# BOTTOM-BOARD_SCH.net
KiCad netlist of a schematic drawn in EAGLE
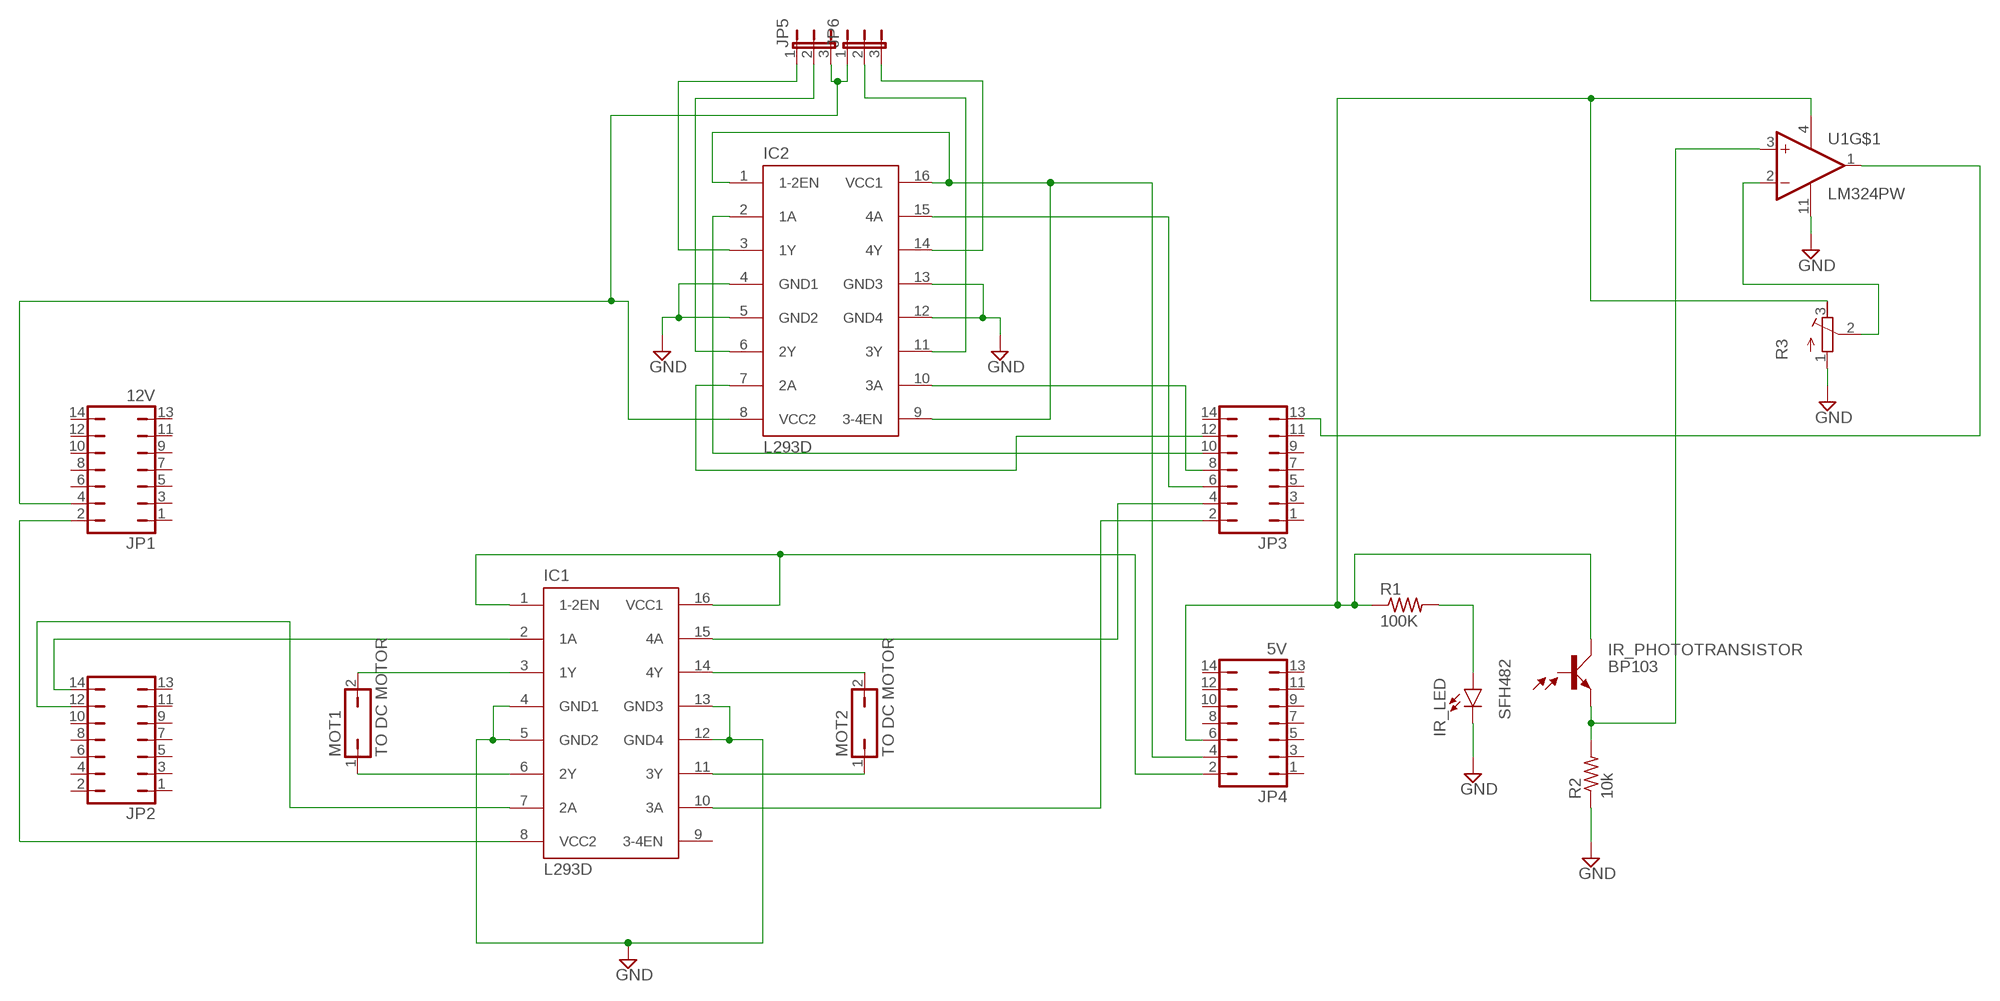
[diagram p0: schematic, sheet 1]

(export (version "E")
  (design (tool "Eeschema 10.0.6"))
  (components
    (comp (ref "IC1")
      (value "L293D")
      (footprint "eagle-import:DIL16")
      (libsource (lib "eagle-import") (part "L293D"))
    )
    (comp (ref "IC2")
      (value "L293D")
      (footprint "eagle-import:DIL16")
      (libsource (lib "eagle-import") (part "L293D"))
    )
    (comp (ref "IR_LED")
      (value "SFH482")
      (footprint "eagle-import:SFH482")
      (libsource (lib "eagle-import") (part "SFH482"))
    )
    (comp (ref "IR_PHOTOTRANSISTOR")
      (value "BP103")
      (footprint "eagle-import:BP103")
      (libsource (lib "eagle-import") (part "BP103"))
    )
    (comp (ref "JP1")
      (value "12V")
      (footprint "eagle-import:JP7Q")
      (libsource (lib "eagle-import") (part "JP7Q"))
    )
    (comp (ref "JP2")
      (value "JP7Q")
      (footprint "eagle-import:JP7Q")
      (libsource (lib "eagle-import") (part "JP7Q"))
    )
    (comp (ref "JP3")
      (value "JP7Q")
      (footprint "eagle-import:JP7Q")
      (libsource (lib "eagle-import") (part "JP7Q"))
    )
    (comp (ref "JP4")
      (value "5V")
      (footprint "eagle-import:JP7Q")
      (libsource (lib "eagle-import") (part "JP7Q"))
    )
    (comp (ref "JP5")
      (value "JP2E")
      (footprint "eagle-import:JP2")
      (libsource (lib "eagle-import") (part "JP2E"))
    )
    (comp (ref "JP6")
      (value "JP2E")
      (footprint "eagle-import:JP2")
      (libsource (lib "eagle-import") (part "JP2E"))
    )
    (comp (ref "MOT1")
      (value "TO DC MOTOR")
      (footprint "eagle-import:JP1")
      (libsource (lib "eagle-import") (part "JP1Q"))
    )
    (comp (ref "MOT2")
      (value "TO DC MOTOR")
      (footprint "eagle-import:JP1")
      (libsource (lib "eagle-import") (part "JP1Q"))
    )
    (comp (ref "R1")
      (value "100K")
      (footprint "eagle-import:0204_5")
      (libsource (lib "eagle-import") (part "R-US_0204/5"))
    )
    (comp (ref "R2")
      (value "10k")
      (footprint "eagle-import:0204_5")
      (libsource (lib "eagle-import") (part "R-US_0204/5"))
    )
    (comp (ref "R3")
      (value "R-TRIMMTSM53YL")
      (footprint "eagle-import:RTRIMTSM53YL")
      (libsource (lib "eagle-import") (part "R-TRIMMTSM53YL"))
    )
    (comp (ref "U1")
      (value "LM324PW")
      (footprint "eagle-import:SOP65P640X120-14N")
      (fields (field (name "MF") "Texas Instruments"))
      (libsource (lib "eagle-import") (part "LM324PW"))
    )
  )
  (nets
    (net (code "1") (name "GND") (class "Default")
      (node (ref "IC1") (pin "12") (pinfunction "GND4_12") (pintype "power_in"))
      (node (ref "IC1") (pin "13") (pinfunction "GND3_13") (pintype "power_in"))
      (node (ref "IC1") (pin "4") (pinfunction "GND1_4") (pintype "power_in"))
      (node (ref "IC1") (pin "5") (pinfunction "GND2_5") (pintype "power_in"))
      (node (ref "IC2") (pin "12") (pinfunction "GND4_12") (pintype "power_in"))
      (node (ref "IC2") (pin "13") (pinfunction "GND3_13") (pintype "power_in"))
      (node (ref "IC2") (pin "4") (pinfunction "GND1_4") (pintype "power_in"))
      (node (ref "IC2") (pin "5") (pinfunction "GND2_5") (pintype "power_in"))
      (node (ref "IR_LED") (pin "K") (pinfunction "C_K") (pintype "passive"))
      (node (ref "R2") (pin "1") (pinfunction "1_1") (pintype "passive"))
      (node (ref "R3") (pin "1") (pinfunction "A_1") (pintype "passive"))
      (node (ref "U1") (pin "11") (pinfunction "GND_11") (pintype "power_in"))
    )
    (net (code "2") (name "Net-(IC1-1-2EN)") (class "Default")
      (node (ref "IC1") (pin "1") (pinfunction "1-2EN_1") (pintype "input"))
      (node (ref "IC1") (pin "16") (pinfunction "VCC1_16") (pintype "power_in"))
      (node (ref "JP4") (pin "2") (pinfunction "2_2") (pintype "passive"))
    )
    (net (code "3") (name "Net-(IC1-1A)") (class "Default")
      (node (ref "IC1") (pin "2") (pinfunction "1A_2") (pintype "input"))
      (node (ref "JP2") (pin "14") (pinfunction "14_14") (pintype "passive"))
    )
    (net (code "4") (name "Net-(IC1-1Y)") (class "Default")
      (node (ref "IC1") (pin "3") (pinfunction "1Y_3") (pintype "output"))
      (node (ref "MOT1") (pin "2") (pinfunction "2_2") (pintype "passive"))
    )
    (net (code "5") (name "Net-(IC1-2A)") (class "Default")
      (node (ref "IC1") (pin "7") (pinfunction "2A_7") (pintype "input"))
      (node (ref "JP2") (pin "12") (pinfunction "12_12") (pintype "passive"))
    )
    (net (code "6") (name "Net-(IC1-2Y)") (class "Default")
      (node (ref "IC1") (pin "6") (pinfunction "2Y_6") (pintype "output"))
      (node (ref "MOT1") (pin "1") (pinfunction "1_1") (pintype "passive"))
    )
    (net (code "7") (name "Net-(IC1-3A)") (class "Default")
      (node (ref "IC1") (pin "10") (pinfunction "3A_10") (pintype "input"))
      (node (ref "JP3") (pin "2") (pinfunction "2_2") (pintype "passive"))
    )
    (net (code "8") (name "Net-(IC1-3Y)") (class "Default")
      (node (ref "IC1") (pin "11") (pinfunction "3Y_11") (pintype "output"))
      (node (ref "MOT2") (pin "1") (pinfunction "1_1") (pintype "passive"))
    )
    (net (code "9") (name "Net-(IC1-4A)") (class "Default")
      (node (ref "IC1") (pin "15") (pinfunction "4A_15") (pintype "input"))
      (node (ref "JP3") (pin "4") (pinfunction "4_4") (pintype "passive"))
    )
    (net (code "10") (name "Net-(IC1-4Y)") (class "Default")
      (node (ref "IC1") (pin "14") (pinfunction "4Y_14") (pintype "output"))
      (node (ref "MOT2") (pin "2") (pinfunction "2_2") (pintype "passive"))
    )
    (net (code "11") (name "Net-(IC1-VCC2)") (class "Default")
      (node (ref "IC1") (pin "8") (pinfunction "VCC2_8") (pintype "power_in"))
      (node (ref "JP1") (pin "2") (pinfunction "2_2") (pintype "passive"))
    )
    (net (code "12") (name "Net-(IC2-1-2EN)") (class "Default")
      (node (ref "IC2") (pin "1") (pinfunction "1-2EN_1") (pintype "input"))
      (node (ref "IC2") (pin "16") (pinfunction "VCC1_16") (pintype "power_in"))
      (node (ref "IC2") (pin "9") (pinfunction "3-4EN_9") (pintype "input"))
      (node (ref "JP4") (pin "4") (pinfunction "4_4") (pintype "passive"))
    )
    (net (code "13") (name "Net-(IC2-1A)") (class "Default")
      (node (ref "IC2") (pin "2") (pinfunction "1A_2") (pintype "input"))
      (node (ref "JP3") (pin "10") (pinfunction "10_10") (pintype "passive"))
    )
    (net (code "14") (name "Net-(IC2-1Y)") (class "Default")
      (node (ref "IC2") (pin "3") (pinfunction "1Y_3") (pintype "output"))
      (node (ref "JP5") (pin "1") (pinfunction "1_1") (pintype "passive"))
    )
    (net (code "15") (name "Net-(IC2-2A)") (class "Default")
      (node (ref "IC2") (pin "7") (pinfunction "2A_7") (pintype "input"))
      (node (ref "JP3") (pin "12") (pinfunction "12_12") (pintype "passive"))
    )
    (net (code "16") (name "Net-(IC2-2Y)") (class "Default")
      (node (ref "IC2") (pin "6") (pinfunction "2Y_6") (pintype "output"))
      (node (ref "JP5") (pin "2") (pinfunction "2_2") (pintype "passive"))
    )
    (net (code "17") (name "Net-(IC2-3A)") (class "Default")
      (node (ref "IC2") (pin "10") (pinfunction "3A_10") (pintype "input"))
      (node (ref "JP3") (pin "8") (pinfunction "8_8") (pintype "passive"))
    )
    (net (code "18") (name "Net-(IC2-3Y)") (class "Default")
      (node (ref "IC2") (pin "11") (pinfunction "3Y_11") (pintype "output"))
      (node (ref "JP6") (pin "2") (pinfunction "2_2") (pintype "passive"))
    )
    (net (code "19") (name "Net-(IC2-4A)") (class "Default")
      (node (ref "IC2") (pin "15") (pinfunction "4A_15") (pintype "input"))
      (node (ref "JP3") (pin "6") (pinfunction "6_6") (pintype "passive"))
    )
    (net (code "20") (name "Net-(IC2-4Y)") (class "Default")
      (node (ref "IC2") (pin "14") (pinfunction "4Y_14") (pintype "output"))
      (node (ref "JP6") (pin "3") (pinfunction "3_3") (pintype "passive"))
    )
    (net (code "21") (name "Net-(IC2-VCC2)") (class "Default")
      (node (ref "IC2") (pin "8") (pinfunction "VCC2_8") (pintype "power_in"))
      (node (ref "JP1") (pin "4") (pinfunction "4_4") (pintype "passive"))
      (node (ref "JP5") (pin "3") (pinfunction "3_3") (pintype "passive"))
      (node (ref "JP6") (pin "1") (pinfunction "1_1") (pintype "passive"))
    )
    (net (code "22") (name "Net-(IR_LED-PadA)") (class "Default")
      (node (ref "IR_LED") (pin "A") (pinfunction "A_A") (pintype "passive"))
      (node (ref "R1") (pin "2") (pinfunction "2_2") (pintype "passive"))
    )
    (net (code "23") (name "Net-(R3-E)") (class "Default")
      (node (ref "IR_PHOTOTRANSISTOR") (pin "C") (pinfunction "C_C") (pintype "passive"))
      (node (ref "JP4") (pin "6") (pinfunction "6_6") (pintype "passive"))
      (node (ref "R1") (pin "1") (pinfunction "1_1") (pintype "passive"))
      (node (ref "R3") (pin "3") (pinfunction "E_3") (pintype "passive"))
      (node (ref "U1") (pin "4") (pinfunction "VCC_4") (pintype "power_in"))
    )
    (net (code "24") (name "Net-(R3-S)") (class "Default")
      (node (ref "R3") (pin "2") (pinfunction "S_2") (pintype "passive"))
      (node (ref "U1") (pin "2") (pinfunction "-IN1_2") (pintype "input"))
    )
    (net (code "25") (name "Net-(U1A-+IN1)") (class "Default")
      (node (ref "IR_PHOTOTRANSISTOR") (pin "E") (pinfunction "E_E") (pintype "passive"))
      (node (ref "R2") (pin "2") (pinfunction "2_2") (pintype "passive"))
      (node (ref "U1") (pin "3") (pinfunction "+IN1_3") (pintype "input"))
    )
    (net (code "26") (name "Net-(U1A-OUT1)") (class "Default")
      (node (ref "JP3") (pin "13") (pinfunction "13_13") (pintype "passive"))
      (node (ref "U1") (pin "1") (pinfunction "OUT1_1") (pintype "output"))
    )
    (net (code "27") (name "unconnected-(IC1-3-4EN-Pad9)") (class "Default")
      (node (ref "IC1") (pin "9") (pinfunction "3-4EN_9") (pintype "input"))
    )
    (net (code "28") (name "unconnected-(IR_PHOTOTRANSISTOR-PadB)") (class "Default")
      (node (ref "IR_PHOTOTRANSISTOR") (pin "B") (pinfunction "B_B") (pintype "passive"))
    )
    (net (code "29") (name "unconnected-(JP1-Pad1)") (class "Default")
      (node (ref "JP1") (pin "1") (pinfunction "1_1") (pintype "passive"))
    )
    (net (code "30") (name "unconnected-(JP1-Pad3)") (class "Default")
      (node (ref "JP1") (pin "3") (pinfunction "3_3") (pintype "passive"))
    )
    (net (code "31") (name "unconnected-(JP1-Pad5)") (class "Default")
      (node (ref "JP1") (pin "5") (pinfunction "5_5") (pintype "passive"))
    )
    (net (code "32") (name "unconnected-(JP1-Pad6)") (class "Default")
      (node (ref "JP1") (pin "6") (pinfunction "6_6") (pintype "passive"))
    )
    (net (code "33") (name "unconnected-(JP1-Pad7)") (class "Default")
      (node (ref "JP1") (pin "7") (pinfunction "7_7") (pintype "passive"))
    )
    (net (code "34") (name "unconnected-(JP1-Pad8)") (class "Default")
      (node (ref "JP1") (pin "8") (pinfunction "8_8") (pintype "passive"))
    )
    (net (code "35") (name "unconnected-(JP1-Pad9)") (class "Default")
      (node (ref "JP1") (pin "9") (pinfunction "9_9") (pintype "passive"))
    )
    (net (code "36") (name "unconnected-(JP1-Pad10)") (class "Default")
      (node (ref "JP1") (pin "10") (pinfunction "10_10") (pintype "passive"))
    )
    (net (code "37") (name "unconnected-(JP1-Pad11)") (class "Default")
      (node (ref "JP1") (pin "11") (pinfunction "11_11") (pintype "passive"))
    )
    (net (code "38") (name "unconnected-(JP1-Pad12)") (class "Default")
      (node (ref "JP1") (pin "12") (pinfunction "12_12") (pintype "passive"))
    )
    (net (code "39") (name "unconnected-(JP1-Pad13)") (class "Default")
      (node (ref "JP1") (pin "13") (pinfunction "13_13") (pintype "passive"))
    )
    (net (code "40") (name "unconnected-(JP1-Pad14)") (class "Default")
      (node (ref "JP1") (pin "14") (pinfunction "14_14") (pintype "passive"))
    )
    (net (code "41") (name "unconnected-(JP2-Pad1)") (class "Default")
      (node (ref "JP2") (pin "1") (pinfunction "1_1") (pintype "passive"))
    )
    (net (code "42") (name "unconnected-(JP2-Pad2)") (class "Default")
      (node (ref "JP2") (pin "2") (pinfunction "2_2") (pintype "passive"))
    )
    (net (code "43") (name "unconnected-(JP2-Pad3)") (class "Default")
      (node (ref "JP2") (pin "3") (pinfunction "3_3") (pintype "passive"))
    )
    (net (code "44") (name "unconnected-(JP2-Pad4)") (class "Default")
      (node (ref "JP2") (pin "4") (pinfunction "4_4") (pintype "passive"))
    )
    (net (code "45") (name "unconnected-(JP2-Pad5)") (class "Default")
      (node (ref "JP2") (pin "5") (pinfunction "5_5") (pintype "passive"))
    )
    (net (code "46") (name "unconnected-(JP2-Pad6)") (class "Default")
      (node (ref "JP2") (pin "6") (pinfunction "6_6") (pintype "passive"))
    )
    (net (code "47") (name "unconnected-(JP2-Pad7)") (class "Default")
      (node (ref "JP2") (pin "7") (pinfunction "7_7") (pintype "passive"))
    )
    (net (code "48") (name "unconnected-(JP2-Pad8)") (class "Default")
      (node (ref "JP2") (pin "8") (pinfunction "8_8") (pintype "passive"))
    )
    (net (code "49") (name "unconnected-(JP2-Pad9)") (class "Default")
      (node (ref "JP2") (pin "9") (pinfunction "9_9") (pintype "passive"))
    )
    (net (code "50") (name "unconnected-(JP2-Pad10)") (class "Default")
      (node (ref "JP2") (pin "10") (pinfunction "10_10") (pintype "passive"))
    )
    (net (code "51") (name "unconnected-(JP2-Pad11)") (class "Default")
      (node (ref "JP2") (pin "11") (pinfunction "11_11") (pintype "passive"))
    )
    (net (code "52") (name "unconnected-(JP2-Pad13)") (class "Default")
      (node (ref "JP2") (pin "13") (pinfunction "13_13") (pintype "passive"))
    )
    (net (code "53") (name "unconnected-(JP3-Pad1)") (class "Default")
      (node (ref "JP3") (pin "1") (pinfunction "1_1") (pintype "passive"))
    )
    (net (code "54") (name "unconnected-(JP3-Pad3)") (class "Default")
      (node (ref "JP3") (pin "3") (pinfunction "3_3") (pintype "passive"))
    )
    (net (code "55") (name "unconnected-(JP3-Pad5)") (class "Default")
      (node (ref "JP3") (pin "5") (pinfunction "5_5") (pintype "passive"))
    )
    (net (code "56") (name "unconnected-(JP3-Pad7)") (class "Default")
      (node (ref "JP3") (pin "7") (pinfunction "7_7") (pintype "passive"))
    )
    (net (code "57") (name "unconnected-(JP3-Pad9)") (class "Default")
      (node (ref "JP3") (pin "9") (pinfunction "9_9") (pintype "passive"))
    )
    (net (code "58") (name "unconnected-(JP3-Pad11)") (class "Default")
      (node (ref "JP3") (pin "11") (pinfunction "11_11") (pintype "passive"))
    )
    (net (code "59") (name "unconnected-(JP3-Pad14)") (class "Default")
      (node (ref "JP3") (pin "14") (pinfunction "14_14") (pintype "passive"))
    )
    (net (code "60") (name "unconnected-(JP4-Pad1)") (class "Default")
      (node (ref "JP4") (pin "1") (pinfunction "1_1") (pintype "passive"))
    )
    (net (code "61") (name "unconnected-(JP4-Pad3)") (class "Default")
      (node (ref "JP4") (pin "3") (pinfunction "3_3") (pintype "passive"))
    )
    (net (code "62") (name "unconnected-(JP4-Pad5)") (class "Default")
      (node (ref "JP4") (pin "5") (pinfunction "5_5") (pintype "passive"))
    )
    (net (code "63") (name "unconnected-(JP4-Pad7)") (class "Default")
      (node (ref "JP4") (pin "7") (pinfunction "7_7") (pintype "passive"))
    )
    (net (code "64") (name "unconnected-(JP4-Pad8)") (class "Default")
      (node (ref "JP4") (pin "8") (pinfunction "8_8") (pintype "passive"))
    )
    (net (code "65") (name "unconnected-(JP4-Pad9)") (class "Default")
      (node (ref "JP4") (pin "9") (pinfunction "9_9") (pintype "passive"))
    )
    (net (code "66") (name "unconnected-(JP4-Pad10)") (class "Default")
      (node (ref "JP4") (pin "10") (pinfunction "10_10") (pintype "passive"))
    )
    (net (code "67") (name "unconnected-(JP4-Pad11)") (class "Default")
      (node (ref "JP4") (pin "11") (pinfunction "11_11") (pintype "passive"))
    )
    (net (code "68") (name "unconnected-(JP4-Pad12)") (class "Default")
      (node (ref "JP4") (pin "12") (pinfunction "12_12") (pintype "passive"))
    )
    (net (code "69") (name "unconnected-(JP4-Pad13)") (class "Default")
      (node (ref "JP4") (pin "13") (pinfunction "13_13") (pintype "passive"))
    )
    (net (code "70") (name "unconnected-(JP4-Pad14)") (class "Default")
      (node (ref "JP4") (pin "14") (pinfunction "14_14") (pintype "passive"))
    )
  )
)
